# Placa-Mae-Sch1.net
KiCad netlist of a schematic drawn in Altium Designer
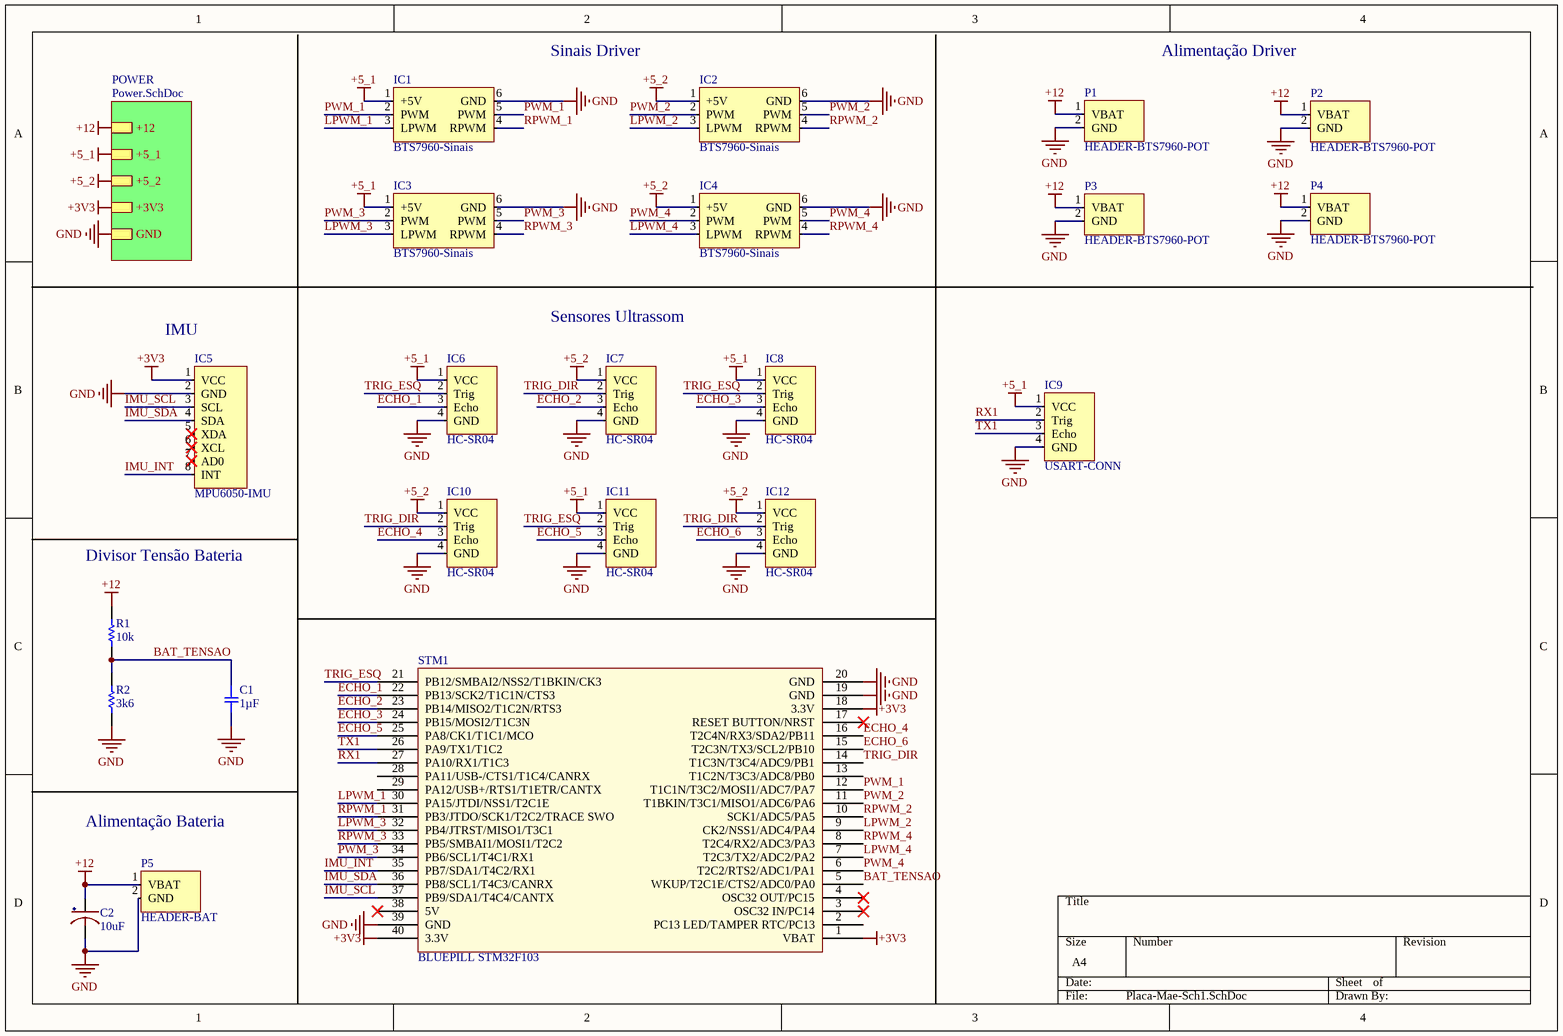
[diagram p0: Placa-Mae-Sch1.SchDoc]

(export (version "E")
  (design (tool "Eeschema 10.0.6"))
  (components
    (comp (ref "C1")
      (value "1µF")
      (footprint "CAPC1608X90N")
      (description "CAP CER 0.1UF 16V X7R 0603")
      (fields
        (field (name "DIGI-KEY PART NUMBER") "490-5796-1-ND")
        (field (name "PART NUMBER") "GCJ188R71C104KA01D")
      )
      (libsource (lib "capacitor_murata_0603") (part "GCJ188R71C104KA01D"))
    )
    (comp (ref "C2")
      (value "10uF")
      (footprint "CAP ALUM 5X5")
      (description "Aluminum Electrolytic Capacitors - SMD 25volts 10uF 5x5.4 20%")
      (fields (field (name "MFR") "Nichion"))
      (libsource (lib "Schlib-Placa-Mae") (part "CAP ALUM 25V 10uF"))
    )
    (comp (ref "IC1")
      (value "BTS7960-Sinais")
      (footprint "HEADER 3X2 M")
      (description "Conector com os sinais de controle de velocidade do driver BTS7960")
      (libsource (lib "Schlib-Placa-Mae") (part "BTS7960-Sinais"))
    )
    (comp (ref "IC2")
      (value "BTS7960-Sinais")
      (footprint "HEADER 3X2 M")
      (description "Conector com os sinais de controle de velocidade do driver BTS7960")
      (libsource (lib "Schlib-Placa-Mae") (part "BTS7960-Sinais"))
    )
    (comp (ref "IC3")
      (value "BTS7960-Sinais")
      (footprint "HEADER 3X2 M")
      (description "Conector com os sinais de controle de velocidade do driver BTS7960")
      (libsource (lib "Schlib-Placa-Mae") (part "BTS7960-Sinais"))
    )
    (comp (ref "IC4")
      (value "BTS7960-Sinais")
      (footprint "HEADER 3X2 M")
      (description "Conector com os sinais de controle de velocidade do driver BTS7960")
      (libsource (lib "Schlib-Placa-Mae") (part "BTS7960-Sinais"))
    )
    (comp (ref "IC5")
      (value "MPU6050-IMU")
      (footprint "MPU6050-IMU")
      (libsource (lib "Schlib-Placa-Mae") (part "MPU6050-IMU"))
    )
    (comp (ref "IC6")
      (value "HC-SR04")
      (footprint "HEADER 1X4 F")
      (description "Sensor Ultrassom")
      (libsource (lib "Schlib-Placa-Mae") (part "HC-SR04"))
    )
    (comp (ref "IC7")
      (value "HC-SR04")
      (footprint "HEADER 1X4 F")
      (description "Sensor Ultrassom")
      (libsource (lib "Schlib-Placa-Mae") (part "HC-SR04"))
    )
    (comp (ref "IC8")
      (value "HC-SR04")
      (footprint "HEADER 1X4 F")
      (description "Sensor Ultrassom")
      (libsource (lib "Schlib-Placa-Mae") (part "HC-SR04"))
    )
    (comp (ref "IC9")
      (value "USART-CONN")
      (footprint "HEADER 1X4 F")
      (description "Sensor Ultrassom")
      (libsource (lib "Schlib-Placa-Mae") (part "HC-SR04"))
    )
    (comp (ref "IC10")
      (value "HC-SR04")
      (footprint "HEADER 1X4 F")
      (description "Sensor Ultrassom")
      (libsource (lib "Schlib-Placa-Mae") (part "HC-SR04"))
    )
    (comp (ref "IC11")
      (value "HC-SR04")
      (footprint "HEADER 1X4 F")
      (description "Sensor Ultrassom")
      (libsource (lib "Schlib-Placa-Mae") (part "HC-SR04"))
    )
    (comp (ref "IC12")
      (value "HC-SR04")
      (footprint "HEADER 1X4 F")
      (description "Sensor Ultrassom")
      (libsource (lib "Schlib-Placa-Mae") (part "HC-SR04"))
    )
    (comp (ref "P1")
      (value "HEADER-BTS7960-POT")
      (footprint "XT60-Male")
      (libsource (lib "Schlib-Placa-Mae") (part "HEADER-BTS7960-POT"))
    )
    (comp (ref "P2")
      (value "HEADER-BTS7960-POT")
      (footprint "XT60-Male")
      (libsource (lib "Schlib-Placa-Mae") (part "HEADER-BTS7960-POT"))
    )
    (comp (ref "P3")
      (value "HEADER-BTS7960-POT")
      (footprint "XT60-Male")
      (libsource (lib "Schlib-Placa-Mae") (part "HEADER-BTS7960-POT"))
    )
    (comp (ref "P4")
      (value "HEADER-BTS7960-POT")
      (footprint "XT60-Male")
      (libsource (lib "Schlib-Placa-Mae") (part "HEADER-BTS7960-POT"))
    )
    (comp (ref "P5")
      (value "HEADER-BAT")
      (footprint "XT60-Male")
      (libsource (lib "Schlib-Placa-Mae") (part "HEADER-BAT"))
    )
    (comp (ref "R1")
      (value "10k")
      (footprint "RESC1608X55N")
      (description "RES SMD 20 OHM 1% 1/16W 0603")
      (libsource (lib "Schlib1") (part "RES 1K 0402"))
    )
    (comp (ref "R2")
      (value "3k6")
      (footprint "RESC1608X55N")
      (description "RES SMD 20 OHM 1% 1/16W 0603")
      (libsource (lib "Schlib1") (part "RES 1K 0402"))
    )
    (comp (ref "STM1")
      (value "BLUEPILL STM32F103")
      (footprint "STM32-BLUEPILL")
      (description "STM32 Blue Pill Development Module")
      (libsource (lib "Schlib-Placa-Mae") (part "STM32-BLUEPILL"))
    )
  )
  (nets
    (net (code "1") (name "+3V3") (class "Default")
      (node (ref "IC5") (pin "1") (pinfunction "VCC_1") (pintype "passive"))
      (node (ref "STM1") (pin "1") (pinfunction "VBAT_1") (pintype "passive"))
      (node (ref "STM1") (pin "18") (pinfunction "3.3V_18") (pintype "passive"))
      (node (ref "STM1") (pin "40") (pinfunction "3.3V_40") (pintype "passive"))
    )
    (net (code "2") (name "+5_1") (class "Default")
      (node (ref "IC1") (pin "1") (pinfunction "+5V_1") (pintype "passive"))
      (node (ref "IC11") (pin "1") (pinfunction "VCC_1") (pintype "passive"))
      (node (ref "IC3") (pin "1") (pinfunction "+5V_1") (pintype "passive"))
      (node (ref "IC6") (pin "1") (pinfunction "VCC_1") (pintype "passive"))
      (node (ref "IC8") (pin "1") (pinfunction "VCC_1") (pintype "passive"))
      (node (ref "IC9") (pin "1") (pinfunction "VCC_1") (pintype "passive"))
    )
    (net (code "3") (name "+5_2") (class "Default")
      (node (ref "IC10") (pin "1") (pinfunction "VCC_1") (pintype "passive"))
      (node (ref "IC12") (pin "1") (pinfunction "VCC_1") (pintype "passive"))
      (node (ref "IC2") (pin "1") (pinfunction "+5V_1") (pintype "passive"))
      (node (ref "IC4") (pin "1") (pinfunction "+5V_1") (pintype "passive"))
      (node (ref "IC7") (pin "1") (pinfunction "VCC_1") (pintype "passive"))
    )
    (net (code "4") (name "+12") (class "Default")
      (node (ref "C2") (pin "1") (pinfunction "1_1") (pintype "passive"))
      (node (ref "P1") (pin "1") (pinfunction "VBAT_1") (pintype "passive"))
      (node (ref "P2") (pin "1") (pinfunction "VBAT_1") (pintype "passive"))
      (node (ref "P3") (pin "1") (pinfunction "VBAT_1") (pintype "passive"))
      (node (ref "P4") (pin "1") (pinfunction "VBAT_1") (pintype "passive"))
      (node (ref "P5") (pin "1") (pinfunction "VBAT_1") (pintype "passive"))
      (node (ref "R1") (pin "2") (pinfunction "2_2") (pintype "passive"))
    )
    (net (code "5") (name "/BAT_TENSAO") (class "Default")
      (node (ref "C1") (pin "1") (pinfunction "1_1") (pintype "passive"))
      (node (ref "R1") (pin "1") (pinfunction "1_1") (pintype "passive"))
      (node (ref "R2") (pin "2") (pinfunction "2_2") (pintype "passive"))
      (node (ref "STM1") (pin "5") (pinfunction "WKUP/T2C1E/CTS2/ADC0/PA0_5") (pintype "passive"))
    )
    (net (code "6") (name "/ECHO_1") (class "Default")
      (node (ref "IC6") (pin "3") (pinfunction "Echo_3") (pintype "passive"))
      (node (ref "STM1") (pin "22") (pinfunction "PB13/SCK2/T1C1N/CTS3_22") (pintype "passive"))
    )
    (net (code "7") (name "/ECHO_2") (class "Default")
      (node (ref "IC7") (pin "3") (pinfunction "Echo_3") (pintype "passive"))
      (node (ref "STM1") (pin "23") (pinfunction "PB14/MISO2/T1C2N/RTS3_23") (pintype "passive"))
    )
    (net (code "8") (name "/ECHO_3") (class "Default")
      (node (ref "IC8") (pin "3") (pinfunction "Echo_3") (pintype "passive"))
      (node (ref "STM1") (pin "24") (pinfunction "PB15/MOSI2/T1C3N_24") (pintype "passive"))
    )
    (net (code "9") (name "/ECHO_4") (class "Default")
      (node (ref "IC10") (pin "3") (pinfunction "Echo_3") (pintype "passive"))
      (node (ref "STM1") (pin "16") (pinfunction "T2C4N/RX3/SDA2/PB11_16") (pintype "passive"))
    )
    (net (code "10") (name "/ECHO_5") (class "Default")
      (node (ref "IC11") (pin "3") (pinfunction "Echo_3") (pintype "passive"))
      (node (ref "STM1") (pin "25") (pinfunction "PA8/CK1/T1C1/MCO_25") (pintype "passive"))
    )
    (net (code "11") (name "/ECHO_6") (class "Default")
      (node (ref "IC12") (pin "3") (pinfunction "Echo_3") (pintype "passive"))
      (node (ref "STM1") (pin "15") (pinfunction "T2C3N/TX3/SCL2/PB10_15") (pintype "passive"))
    )
    (net (code "12") (name "/IMU_INT") (class "Default")
      (node (ref "IC5") (pin "8") (pinfunction "INT_8") (pintype "passive"))
      (node (ref "STM1") (pin "35") (pinfunction "PB7/SDA1/T4C2/RX1_35") (pintype "passive"))
    )
    (net (code "13") (name "/IMU_SCL") (class "Default")
      (node (ref "IC5") (pin "3") (pinfunction "SCL_3") (pintype "passive"))
      (node (ref "STM1") (pin "37") (pinfunction "PB9/SDA1/T4C4/CANTX_37") (pintype "passive"))
    )
    (net (code "14") (name "/IMU_SDA") (class "Default")
      (node (ref "IC5") (pin "4") (pinfunction "SDA_4") (pintype "passive"))
      (node (ref "STM1") (pin "36") (pinfunction "PB8/SCL1/T4C3/CANRX_36") (pintype "passive"))
    )
    (net (code "15") (name "/LPWM_1") (class "Default")
      (node (ref "IC1") (pin "3") (pinfunction "LPWM_3") (pintype "passive"))
      (node (ref "STM1") (pin "30") (pinfunction "PA15/JTDI/NSS1/T2C1E_30") (pintype "passive"))
    )
    (net (code "16") (name "/LPWM_2") (class "Default")
      (node (ref "IC2") (pin "3") (pinfunction "LPWM_3") (pintype "passive"))
      (node (ref "STM1") (pin "9") (pinfunction "CK2/NSS1/ADC4/PA4_9") (pintype "passive"))
    )
    (net (code "17") (name "/LPWM_3") (class "Default")
      (node (ref "IC3") (pin "3") (pinfunction "LPWM_3") (pintype "passive"))
      (node (ref "STM1") (pin "32") (pinfunction "PB4/JTRST/MISO1/T3C1_32") (pintype "passive"))
    )
    (net (code "18") (name "/LPWM_4") (class "Default")
      (node (ref "IC4") (pin "3") (pinfunction "LPWM_3") (pintype "passive"))
      (node (ref "STM1") (pin "7") (pinfunction "T2C3/TX2/ADC2/PA2_7") (pintype "passive"))
    )
    (net (code "19") (name "/PWM_1") (class "Default")
      (node (ref "IC1") (pin "2") (pinfunction "PWM_2") (pintype "passive"))
      (node (ref "IC1") (pin "5") (pinfunction "PWM_5") (pintype "passive"))
      (node (ref "STM1") (pin "12") (pinfunction "T1C1N/T3C2/MOSI1/ADC7/PA7_12") (pintype "passive"))
    )
    (net (code "20") (name "/PWM_2") (class "Default")
      (node (ref "IC2") (pin "2") (pinfunction "PWM_2") (pintype "passive"))
      (node (ref "IC2") (pin "5") (pinfunction "PWM_5") (pintype "passive"))
      (node (ref "STM1") (pin "11") (pinfunction "T1BKIN/T3C1/MISO1/ADC6/PA6_11") (pintype "passive"))
    )
    (net (code "21") (name "/PWM_3") (class "Default")
      (node (ref "IC3") (pin "2") (pinfunction "PWM_2") (pintype "passive"))
      (node (ref "IC3") (pin "5") (pinfunction "PWM_5") (pintype "passive"))
      (node (ref "STM1") (pin "34") (pinfunction "PB6/SCL1/T4C1/RX1_34") (pintype "passive"))
    )
    (net (code "22") (name "/PWM_4") (class "Default")
      (node (ref "IC4") (pin "2") (pinfunction "PWM_2") (pintype "passive"))
      (node (ref "IC4") (pin "5") (pinfunction "PWM_5") (pintype "passive"))
      (node (ref "STM1") (pin "6") (pinfunction "T2C2/RTS2/ADC1/PA1_6") (pintype "passive"))
    )
    (net (code "23") (name "/RPWM_1") (class "Default")
      (node (ref "IC1") (pin "4") (pinfunction "RPWM_4") (pintype "passive"))
      (node (ref "STM1") (pin "31") (pinfunction "PB3/JTDO/SCK1/T2C2/TRACE_SWO_31") (pintype "passive"))
    )
    (net (code "24") (name "/RPWM_2") (class "Default")
      (node (ref "IC2") (pin "4") (pinfunction "RPWM_4") (pintype "passive"))
      (node (ref "STM1") (pin "10") (pinfunction "SCK1/ADC5/PA5_10") (pintype "passive"))
    )
    (net (code "25") (name "/RPWM_3") (class "Default")
      (node (ref "IC3") (pin "4") (pinfunction "RPWM_4") (pintype "passive"))
      (node (ref "STM1") (pin "33") (pinfunction "PB5/SMBAI1/MOSI1/T2C2_33") (pintype "passive"))
    )
    (net (code "26") (name "/RPWM_4") (class "Default")
      (node (ref "IC4") (pin "4") (pinfunction "RPWM_4") (pintype "passive"))
      (node (ref "STM1") (pin "8") (pinfunction "T2C4/RX2/ADC3/PA3_8") (pintype "passive"))
    )
    (net (code "27") (name "/RX1") (class "Default")
      (node (ref "IC9") (pin "2") (pinfunction "Trig_2") (pintype "passive"))
      (node (ref "STM1") (pin "27") (pinfunction "PA10/RX1/T1C3_27") (pintype "passive"))
    )
    (net (code "28") (name "/TRIG_DIR") (class "Default")
      (node (ref "IC10") (pin "2") (pinfunction "Trig_2") (pintype "passive"))
      (node (ref "IC12") (pin "2") (pinfunction "Trig_2") (pintype "passive"))
      (node (ref "IC7") (pin "2") (pinfunction "Trig_2") (pintype "passive"))
      (node (ref "STM1") (pin "14") (pinfunction "T1C3N/T3C4/ADC9/PB1_14") (pintype "passive"))
    )
    (net (code "29") (name "/TRIG_ESQ") (class "Default")
      (node (ref "IC11") (pin "2") (pinfunction "Trig_2") (pintype "passive"))
      (node (ref "IC6") (pin "2") (pinfunction "Trig_2") (pintype "passive"))
      (node (ref "IC8") (pin "2") (pinfunction "Trig_2") (pintype "passive"))
      (node (ref "STM1") (pin "21") (pinfunction "PB12/SMBAI2/NSS2/T1BKIN/CK3_21") (pintype "passive"))
    )
    (net (code "30") (name "/TX1") (class "Default")
      (node (ref "IC9") (pin "3") (pinfunction "Echo_3") (pintype "passive"))
      (node (ref "STM1") (pin "26") (pinfunction "PA9/TX1/T1C2_26") (pintype "passive"))
    )
    (net (code "31") (name "GND") (class "Default")
      (node (ref "C1") (pin "2") (pinfunction "2_2") (pintype "passive"))
      (node (ref "C2") (pin "2") (pinfunction "2_2") (pintype "passive"))
      (node (ref "IC1") (pin "6") (pinfunction "GND_6") (pintype "passive"))
      (node (ref "IC10") (pin "4") (pinfunction "GND_4") (pintype "passive"))
      (node (ref "IC11") (pin "4") (pinfunction "GND_4") (pintype "passive"))
      (node (ref "IC12") (pin "4") (pinfunction "GND_4") (pintype "passive"))
      (node (ref "IC2") (pin "6") (pinfunction "GND_6") (pintype "passive"))
      (node (ref "IC3") (pin "6") (pinfunction "GND_6") (pintype "passive"))
      (node (ref "IC4") (pin "6") (pinfunction "GND_6") (pintype "passive"))
      (node (ref "IC5") (pin "2") (pinfunction "GND_2") (pintype "passive"))
      (node (ref "IC6") (pin "4") (pinfunction "GND_4") (pintype "passive"))
      (node (ref "IC7") (pin "4") (pinfunction "GND_4") (pintype "passive"))
      (node (ref "IC8") (pin "4") (pinfunction "GND_4") (pintype "passive"))
      (node (ref "IC9") (pin "4") (pinfunction "GND_4") (pintype "passive"))
      (node (ref "P1") (pin "2") (pinfunction "GND_2") (pintype "passive"))
      (node (ref "P2") (pin "2") (pinfunction "GND_2") (pintype "passive"))
      (node (ref "P3") (pin "2") (pinfunction "GND_2") (pintype "passive"))
      (node (ref "P4") (pin "2") (pinfunction "GND_2") (pintype "passive"))
      (node (ref "P5") (pin "2") (pinfunction "GND_2") (pintype "passive"))
      (node (ref "R2") (pin "1") (pinfunction "1_1") (pintype "passive"))
      (node (ref "STM1") (pin "19") (pinfunction "GND_19") (pintype "passive"))
      (node (ref "STM1") (pin "20") (pinfunction "GND_20") (pintype "passive"))
      (node (ref "STM1") (pin "39") (pinfunction "GND_39") (pintype "passive"))
    )
    (net (code "32") (name "unconnected-(IC5-AD0-Pad7)") (class "Default")
      (node (ref "IC5") (pin "7") (pinfunction "AD0_7") (pintype "passive+no_connect"))
    )
    (net (code "33") (name "unconnected-(IC5-XCL-Pad6)") (class "Default")
      (node (ref "IC5") (pin "6") (pinfunction "XCL_6") (pintype "passive+no_connect"))
    )
    (net (code "34") (name "unconnected-(IC5-XDA-Pad5)") (class "Default")
      (node (ref "IC5") (pin "5") (pinfunction "XDA_5") (pintype "passive+no_connect"))
    )
    (net (code "35") (name "unconnected-(STM1-5V-Pad38)") (class "Default")
      (node (ref "STM1") (pin "38") (pinfunction "5V_38") (pintype "passive+no_connect"))
    )
    (net (code "36") (name "unconnected-(STM1-OSC32_IN{slash}PC14-Pad3)") (class "Default")
      (node (ref "STM1") (pin "3") (pinfunction "OSC32_IN/PC14_3") (pintype "passive+no_connect"))
    )
    (net (code "37") (name "unconnected-(STM1-OSC32_OUT{slash}PC15-Pad4)") (class "Default")
      (node (ref "STM1") (pin "4") (pinfunction "OSC32_OUT/PC15_4") (pintype "passive+no_connect"))
    )
    (net (code "38") (name "unconnected-(STM1-PA11{slash}USB-{slash}CTS1{slash}T1C4{slash}CANRX-Pad28)") (class "Default")
      (node (ref "STM1") (pin "28") (pinfunction "PA11/USB-/CTS1/T1C4/CANRX_28") (pintype "passive"))
    )
    (net (code "39") (name "unconnected-(STM1-PA12{slash}USB+{slash}RTS1{slash}T1ETR{slash}CANTX-Pad29)") (class "Default")
      (node (ref "STM1") (pin "29") (pinfunction "PA12/USB+/RTS1/T1ETR/CANTX_29") (pintype "passive"))
    )
    (net (code "40") (name "unconnected-(STM1-PC13_LED{slash}TAMPER_RTC{slash}PC13-Pad2)") (class "Default")
      (node (ref "STM1") (pin "2") (pinfunction "PC13_LED/TAMPER_RTC/PC13_2") (pintype "passive"))
    )
    (net (code "41") (name "unconnected-(STM1-RESET_BUTTON{slash}NRST-Pad17)") (class "Default")
      (node (ref "STM1") (pin "17") (pinfunction "RESET_BUTTON/NRST_17") (pintype "passive+no_connect"))
    )
    (net (code "42") (name "unconnected-(STM1-T1C2N{slash}T3C3{slash}ADC8{slash}PB0-Pad13)") (class "Default")
      (node (ref "STM1") (pin "13") (pinfunction "T1C2N/T3C3/ADC8/PB0_13") (pintype "passive"))
    )
  )
)
